# ff555_v2.net
KiCad netlist of a schematic drawn in EAGLE
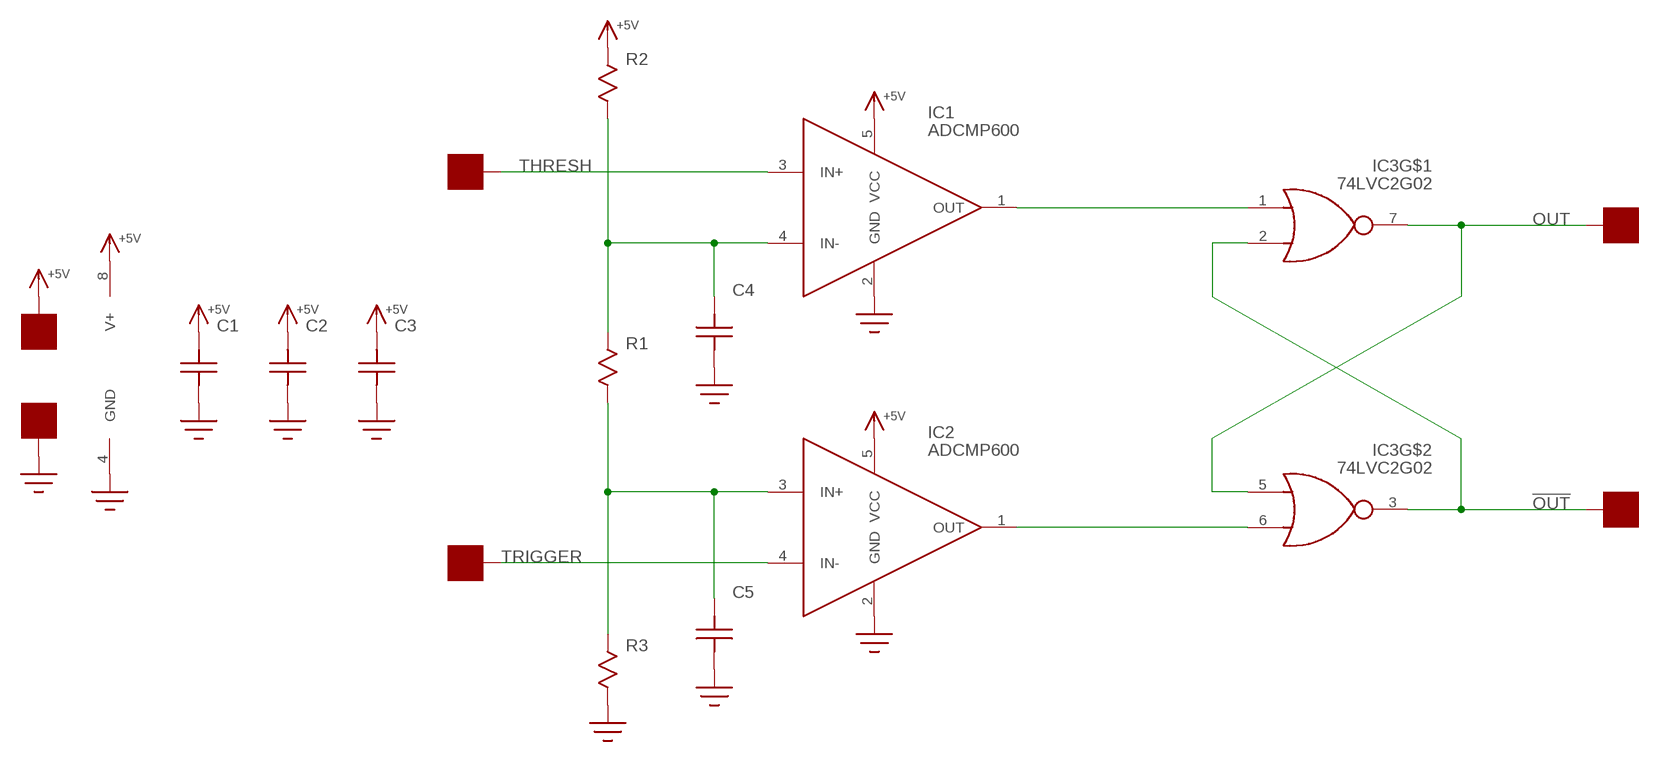
[diagram p0: schematic, sheet 1]

(export (version "E")
  (design (tool "Eeschema 10.0.6"))
  (components
    (comp (ref "C1")
      (value "C0603")
      (footprint "eagle-import:C0603")
      (libsource (lib "eagle-import") (part "C0603"))
    )
    (comp (ref "C2")
      (value "C0603")
      (footprint "eagle-import:C0603")
      (libsource (lib "eagle-import") (part "C0603"))
    )
    (comp (ref "C3")
      (value "C0805")
      (footprint "eagle-import:0805")
      (libsource (lib "eagle-import") (part "C0805"))
    )
    (comp (ref "C4")
      (value "C0603")
      (footprint "eagle-import:C0603")
      (libsource (lib "eagle-import") (part "C0603"))
    )
    (comp (ref "C5")
      (value "C0603")
      (footprint "eagle-import:C0603")
      (libsource (lib "eagle-import") (part "C0603"))
    )
    (comp (ref "IC1")
      (value "ADCMP600")
      (footprint "eagle-import:SOT23-5")
      (libsource (lib "eagle-import") (part "ADCMP600"))
    )
    (comp (ref "IC2")
      (value "ADCMP600")
      (footprint "eagle-import:SOT23-5")
      (libsource (lib "eagle-import") (part "ADCMP600"))
    )
    (comp (ref "IC3")
      (value "74LVC2G02")
      (footprint "eagle-import:TSSOP8")
      (libsource (lib "eagle-import") (part "74LVC2G02"))
    )
    (comp (ref "R1")
      (value "R1206")
      (footprint "eagle-import:R1206")
      (libsource (lib "eagle-import") (part "R1206"))
    )
    (comp (ref "R2")
      (value "R0603")
      (footprint "eagle-import:R0603")
      (libsource (lib "eagle-import") (part "R0603"))
    )
    (comp (ref "R3")
      (value "R0603")
      (footprint "eagle-import:R0603")
      (libsource (lib "eagle-import") (part "R0603"))
    )
    (comp (ref "U$15")
      (value "PAD100MIL")
      (footprint "eagle-import:PAD_100MIL")
      (libsource (lib "eagle-import") (part "PAD100MIL"))
    )
    (comp (ref "U$16")
      (value "PAD100MIL")
      (footprint "eagle-import:PAD_100MIL")
      (libsource (lib "eagle-import") (part "PAD100MIL"))
    )
    (comp (ref "U$17")
      (value "PAD100MIL")
      (footprint "eagle-import:PAD_100MIL")
      (libsource (lib "eagle-import") (part "PAD100MIL"))
    )
    (comp (ref "U$18")
      (value "PAD100MIL")
      (footprint "eagle-import:PAD_100MIL")
      (libsource (lib "eagle-import") (part "PAD100MIL"))
    )
    (comp (ref "U$19")
      (value "PAD100MIL")
      (footprint "eagle-import:PAD_100MIL")
      (libsource (lib "eagle-import") (part "PAD100MIL"))
    )
    (comp (ref "U$20")
      (value "PAD100MIL")
      (footprint "eagle-import:PAD_100MIL")
      (libsource (lib "eagle-import") (part "PAD100MIL"))
    )
  )
  (nets
    (net (code "1") (name "+5V") (class "Default")
      (node (ref "C1") (pin "P$2") (pinfunction "P$2_P$2") (pintype "bidirectional"))
      (node (ref "C2") (pin "P$2") (pinfunction "P$2_P$2") (pintype "bidirectional"))
      (node (ref "C3") (pin "P$2") (pinfunction "P$2_P$2") (pintype "bidirectional"))
      (node (ref "IC1") (pin "5") (pinfunction "VCC_5") (pintype "bidirectional"))
      (node (ref "IC2") (pin "5") (pinfunction "VCC_5") (pintype "bidirectional"))
      (node (ref "IC3") (pin "8") (pinfunction "V+_8") (pintype "bidirectional"))
      (node (ref "R2") (pin "P$1") (pinfunction "P$3_P$1") (pintype "bidirectional"))
      (node (ref "U$15") (pin "P$1") (pinfunction "P$1_P$1") (pintype "bidirectional"))
    )
    (net (code "2") (name "/OUT") (class "Default")
      (node (ref "IC3") (pin "5") (pinfunction "A_5") (pintype "bidirectional"))
      (node (ref "IC3") (pin "7") (pinfunction "Y_7") (pintype "bidirectional"))
      (node (ref "U$19") (pin "P$1") (pinfunction "P$1_P$1") (pintype "bidirectional"))
    )
    (net (code "3") (name "/THRESH") (class "Default")
      (node (ref "IC1") (pin "3") (pinfunction "IN+_3") (pintype "bidirectional"))
      (node (ref "U$17") (pin "P$1") (pinfunction "P$1_P$1") (pintype "bidirectional"))
    )
    (net (code "4") (name "/TRIGGER") (class "Default")
      (node (ref "IC2") (pin "4") (pinfunction "IN-_4") (pintype "bidirectional"))
      (node (ref "U$18") (pin "P$1") (pinfunction "P$1_P$1") (pintype "bidirectional"))
    )
    (net (code "5") (name "/~{OUT}") (class "Default")
      (node (ref "IC3") (pin "2") (pinfunction "B_2") (pintype "bidirectional"))
      (node (ref "IC3") (pin "3") (pinfunction "Y_3") (pintype "bidirectional"))
      (node (ref "U$20") (pin "P$1") (pinfunction "P$1_P$1") (pintype "bidirectional"))
    )
    (net (code "6") (name "GND") (class "Default")
      (node (ref "C1") (pin "P$1") (pinfunction "P$1_P$1") (pintype "bidirectional"))
      (node (ref "C2") (pin "P$1") (pinfunction "P$1_P$1") (pintype "bidirectional"))
      (node (ref "C3") (pin "P$1") (pinfunction "P$1_P$1") (pintype "bidirectional"))
      (node (ref "C4") (pin "P$1") (pinfunction "P$1_P$1") (pintype "bidirectional"))
      (node (ref "C5") (pin "P$1") (pinfunction "P$1_P$1") (pintype "bidirectional"))
      (node (ref "IC1") (pin "2") (pinfunction "GND_2") (pintype "bidirectional"))
      (node (ref "IC2") (pin "2") (pinfunction "GND_2") (pintype "bidirectional"))
      (node (ref "IC3") (pin "4") (pinfunction "GND_4") (pintype "bidirectional"))
      (node (ref "R3") (pin "P$2") (pinfunction "P$4_P$2") (pintype "bidirectional"))
      (node (ref "U$16") (pin "P$1") (pinfunction "P$1_P$1") (pintype "bidirectional"))
    )
    (net (code "7") (name "Net-(IC1-IN-)") (class "Default")
      (node (ref "C4") (pin "P$2") (pinfunction "P$2_P$2") (pintype "bidirectional"))
      (node (ref "IC1") (pin "4") (pinfunction "IN-_4") (pintype "bidirectional"))
      (node (ref "R1") (pin "P$1") (pinfunction "P$3_P$1") (pintype "bidirectional"))
      (node (ref "R2") (pin "P$2") (pinfunction "P$4_P$2") (pintype "bidirectional"))
    )
    (net (code "8") (name "Net-(IC1-OUT)") (class "Default")
      (node (ref "IC1") (pin "1") (pinfunction "OUT_1") (pintype "bidirectional"))
      (node (ref "IC3") (pin "1") (pinfunction "A_1") (pintype "bidirectional"))
    )
    (net (code "9") (name "Net-(IC2-IN+)") (class "Default")
      (node (ref "C5") (pin "P$2") (pinfunction "P$2_P$2") (pintype "bidirectional"))
      (node (ref "IC2") (pin "3") (pinfunction "IN+_3") (pintype "bidirectional"))
      (node (ref "R1") (pin "P$2") (pinfunction "P$4_P$2") (pintype "bidirectional"))
      (node (ref "R3") (pin "P$1") (pinfunction "P$3_P$1") (pintype "bidirectional"))
    )
    (net (code "10") (name "Net-(IC2-OUT)") (class "Default")
      (node (ref "IC2") (pin "1") (pinfunction "OUT_1") (pintype "bidirectional"))
      (node (ref "IC3") (pin "6") (pinfunction "B_6") (pintype "bidirectional"))
    )
  )
)
